# USB_FE1_1.net
KiCad netlist of a schematic drawn in Altium Designer
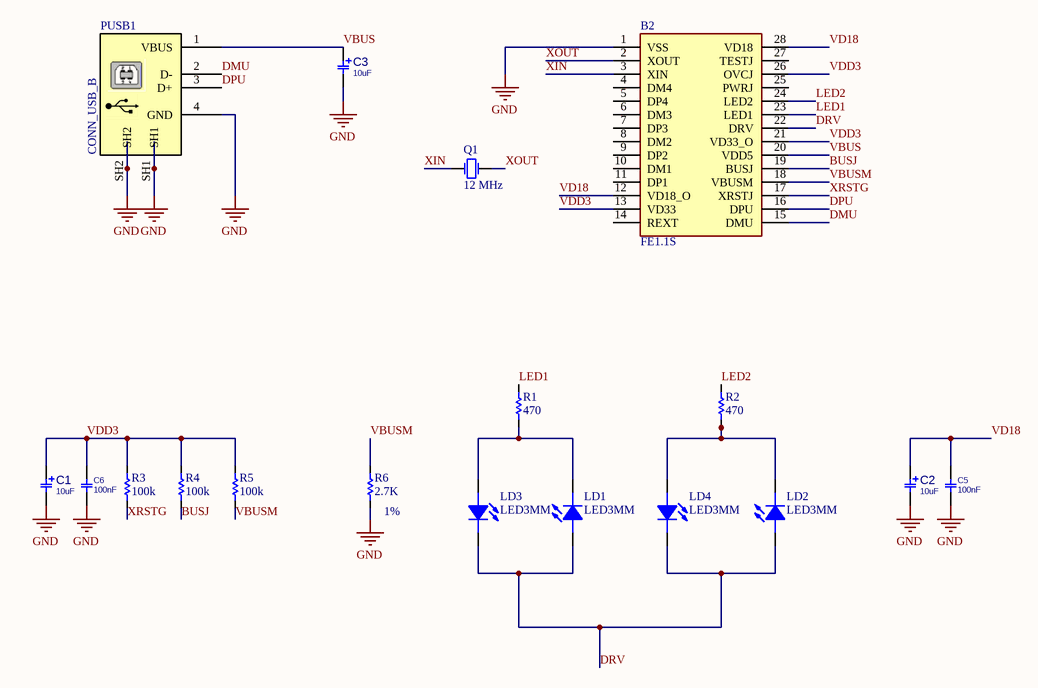
[diagram p0: USB_FE1.1.SchDoc]

(export (version "E")
  (design (tool "Eeschema 10.0.6"))
  (components
    (comp (ref "B2")
      (value "FE1.1S")
      (footprint "SOP64P600X175-28N")
      (description "USB 2.0 HIGH SPEED 4-PORT HUB CONTROLLER")
      (libsource (lib "FE1.1") (part "FE1.1S"))
    )
    (comp (ref "C1")
      (value "10uF")
      (footprint "C_EL_4X7")
      (description "CAP, THD, ELEC,")
      (fields (field (name "MANF_P#") "MANF_PART#") (field (name "MANF") "MANF"))
      (libsource (lib "PASSIVE") (part "CAP_THD_EL"))
    )
    (comp (ref "C2")
      (value "10uF")
      (footprint "C_EL_4X7")
      (description "CAP, THD, ELEC,")
      (fields (field (name "MANF_P#") "MANF_PART#") (field (name "MANF") "MANF"))
      (libsource (lib "PASSIVE") (part "CAP_THD_EL"))
    )
    (comp (ref "C3")
      (value "10uF")
      (footprint "C_EL_4X7")
      (description "CAP, THD, ELEC,")
      (fields (field (name "MANF_P#") "MANF_PART#") (field (name "MANF") "MANF"))
      (libsource (lib "PASSIVE") (part "CAP_THD_EL"))
    )
    (comp (ref "C5")
      (value "100nF")
      (footprint "C_CER_D3")
      (description "CAP, THD, CER MULTI LAYER,")
      (fields (field (name "MANF_P#") "MANF_PART#") (field (name "MANF") "MANF"))
      (libsource (lib "PASSIVE") (part "CAP_THD_CERML"))
    )
    (comp (ref "C6")
      (value "100nF")
      (footprint "C_CER_D3")
      (description "CAP, THD, CER MULTI LAYER,")
      (fields (field (name "MANF_P#") "MANF_PART#") (field (name "MANF") "MANF"))
      (libsource (lib "PASSIVE") (part "CAP_THD_CERML"))
    )
    (comp (ref "LD1")
      (value "LED3MM")
      (footprint "LED3mm_GRN")
      (description "Light Emitting Diode")
      (fields (field (name "DESIGNER") "Ali Hafizi"))
      (libsource (lib "4_5773615018641719593") (part "LED 3MM"))
    )
    (comp (ref "LD2")
      (value "LED3MM")
      (footprint "LED3mm_GRN")
      (description "Light Emitting Diode")
      (fields (field (name "DESIGNER") "Ali Hafizi"))
      (libsource (lib "4_5773615018641719593") (part "LED 3MM"))
    )
    (comp (ref "LD3")
      (value "LED3MM")
      (footprint "LED3mm_GRN")
      (description "Light Emitting Diode")
      (fields (field (name "DESIGNER") "Ali Hafizi"))
      (libsource (lib "4_5773615018641719593") (part "LED 3MM"))
    )
    (comp (ref "LD4")
      (value "LED3MM")
      (footprint "LED3mm_GRN")
      (description "Light Emitting Diode")
      (fields (field (name "DESIGNER") "Ali Hafizi"))
      (libsource (lib "4_5773615018641719593") (part "LED 3MM"))
    )
    (comp (ref "PUSB1")
      (value "CONN_USB_B")
      (footprint "USB_B_RA_THD")
      (description "CONN, USB, B, R/A, THD")
      (fields (field (name "MANF_P#") "292304-1") (field (name "MANF") "TE Connectivity"))
      (libsource (lib "Chila_PCB") (part "CONN_USB_B_RA_THD"))
    )
    (comp (ref "Q1")
      (value "12 MHz")
      (footprint "XTAL 16MHZ")
      (description "XTAL Crystal")
      (fields (field (name "DESIGNER") "ABBAS BASEREH"))
      (libsource (lib "4_5773615018641719593") (part "XTAL"))
    )
    (comp (ref "R1")
      (value "470")
      (footprint "Res-(1/4)")
      (description "Resistor")
      (fields (field (name "TOLERANCE") "5%") (field (name "POWER") "1/4 W"))
      (libsource (lib "altium mahdi") (part "Resistor"))
    )
    (comp (ref "R2")
      (value "470")
      (footprint "Res-(1/4)")
      (description "Resistor")
      (fields (field (name "TOLERANCE") "5%") (field (name "POWER") "1/4 W"))
      (libsource (lib "altium mahdi") (part "Resistor"))
    )
    (comp (ref "R3")
      (value "100k")
      (footprint "Res-(1/4)")
      (description "Resistor")
      (fields (field (name "TOLERANCE") "5%") (field (name "POWER") "1/4 W"))
      (libsource (lib "altium mahdi") (part "Resistor"))
    )
    (comp (ref "R4")
      (value "100k")
      (footprint "Res-(1/4)")
      (description "Resistor")
      (fields (field (name "TOLERANCE") "5%") (field (name "POWER") "1/4 W"))
      (libsource (lib "altium mahdi") (part "Resistor"))
    )
    (comp (ref "R5")
      (value "100k")
      (footprint "Res-(1/4)")
      (description "Resistor")
      (fields (field (name "TOLERANCE") "5%") (field (name "POWER") "1/4 W"))
      (libsource (lib "altium mahdi") (part "Resistor"))
    )
    (comp (ref "R6")
      (value "2.7K")
      (footprint "Res-(1/4)")
      (description "Resistor")
      (fields (field (name "TOLERANCE") "1%") (field (name "POWER") "1/4 W"))
      (libsource (lib "altium mahdi") (part "Resistor"))
    )
  )
  (nets
    (net (code "1") (name "/BUSJ") (class "Default")
      (node (ref "B2") (pin "19") (pinfunction "BUSJ_19") (pintype "passive"))
      (node (ref "R4") (pin "1") (pinfunction "1_1") (pintype "passive"))
    )
    (net (code "2") (name "/DMU") (class "Default")
      (node (ref "B2") (pin "15") (pinfunction "DMU_15") (pintype "passive"))
      (node (ref "PUSB1") (pin "2") (pinfunction "D-_2") (pintype "passive"))
    )
    (net (code "3") (name "/DPU") (class "Default")
      (node (ref "B2") (pin "16") (pinfunction "DPU_16") (pintype "passive"))
      (node (ref "PUSB1") (pin "3") (pinfunction "D+_3") (pintype "passive"))
    )
    (net (code "4") (name "/DRV") (class "Default")
      (node (ref "B2") (pin "22") (pinfunction "DRV_22") (pintype "passive"))
      (node (ref "LD1") (pin "1") (pinfunction "ANODE_1") (pintype "passive"))
      (node (ref "LD2") (pin "1") (pinfunction "ANODE_1") (pintype "passive"))
      (node (ref "LD3") (pin "2") (pinfunction "CATHODE_2") (pintype "passive"))
      (node (ref "LD4") (pin "2") (pinfunction "CATHODE_2") (pintype "passive"))
    )
    (net (code "5") (name "/LED1") (class "Default")
      (node (ref "B2") (pin "23") (pinfunction "LED1_23") (pintype "passive"))
      (node (ref "R1") (pin "2") (pinfunction "2_2") (pintype "passive"))
    )
    (net (code "6") (name "/LED2") (class "Default")
      (node (ref "B2") (pin "24") (pinfunction "LED2_24") (pintype "passive"))
      (node (ref "R2") (pin "2") (pinfunction "2_2") (pintype "passive"))
    )
    (net (code "7") (name "/VBUS") (class "Default")
      (node (ref "B2") (pin "20") (pinfunction "VDD5_20") (pintype "passive"))
      (node (ref "C3") (pin "1") (pinfunction "1_1") (pintype "passive"))
      (node (ref "PUSB1") (pin "1") (pinfunction "VBUS_1") (pintype "power_in"))
    )
    (net (code "8") (name "/VBUSM") (class "Default")
      (node (ref "B2") (pin "18") (pinfunction "VBUSM_18") (pintype "passive"))
      (node (ref "R5") (pin "1") (pinfunction "1_1") (pintype "passive"))
      (node (ref "R6") (pin "2") (pinfunction "2_2") (pintype "passive"))
    )
    (net (code "9") (name "/VD18") (class "Default")
      (node (ref "B2") (pin "12") (pinfunction "VD18_O_12") (pintype "passive"))
      (node (ref "B2") (pin "28") (pinfunction "VD18_28") (pintype "passive"))
      (node (ref "C2") (pin "1") (pinfunction "1_1") (pintype "passive"))
      (node (ref "C5") (pin "2") (pinfunction "2_2") (pintype "passive"))
    )
    (net (code "10") (name "/VDD3") (class "Default")
      (node (ref "B2") (pin "13") (pinfunction "VD33_13") (pintype "passive"))
      (node (ref "B2") (pin "21") (pinfunction "VD33_O_21") (pintype "passive"))
      (node (ref "B2") (pin "26") (pinfunction "OVCJ_26") (pintype "passive"))
      (node (ref "C1") (pin "1") (pinfunction "1_1") (pintype "passive"))
      (node (ref "C6") (pin "2") (pinfunction "2_2") (pintype "passive"))
      (node (ref "R3") (pin "2") (pinfunction "2_2") (pintype "passive"))
      (node (ref "R4") (pin "2") (pinfunction "2_2") (pintype "passive"))
      (node (ref "R5") (pin "2") (pinfunction "2_2") (pintype "passive"))
    )
    (net (code "11") (name "/XIN") (class "Default")
      (node (ref "B2") (pin "3") (pinfunction "XIN_3") (pintype "passive"))
      (node (ref "Q1") (pin "1") (pinfunction "OSC1_1") (pintype "passive"))
    )
    (net (code "12") (name "/XOUT") (class "Default")
      (node (ref "B2") (pin "2") (pinfunction "XOUT_2") (pintype "passive"))
      (node (ref "Q1") (pin "2") (pinfunction "OSC2_2") (pintype "passive"))
    )
    (net (code "13") (name "/XRSTG") (class "Default")
      (node (ref "B2") (pin "17") (pinfunction "XRSTJ_17") (pintype "passive"))
      (node (ref "R3") (pin "1") (pinfunction "1_1") (pintype "passive"))
    )
    (net (code "14") (name "GND") (class "Default")
      (node (ref "B2") (pin "1") (pinfunction "VSS_1") (pintype "passive"))
      (node (ref "C1") (pin "2") (pinfunction "2_2") (pintype "passive"))
      (node (ref "C2") (pin "2") (pinfunction "2_2") (pintype "passive"))
      (node (ref "C3") (pin "2") (pinfunction "2_2") (pintype "passive"))
      (node (ref "C5") (pin "1") (pinfunction "1_1") (pintype "passive"))
      (node (ref "C6") (pin "1") (pinfunction "1_1") (pintype "passive"))
      (node (ref "PUSB1") (pin "4") (pinfunction "GND_4") (pintype "power_in"))
      (node (ref "PUSB1") (pin "SH1") (pinfunction "SH1_SH1") (pintype "passive"))
      (node (ref "PUSB1") (pin "SH2") (pinfunction "SH2_SH2") (pintype "passive"))
      (node (ref "R6") (pin "1") (pinfunction "1_1") (pintype "passive"))
    )
    (net (code "15") (name "Net-(LD1-CATHODE)") (class "Default")
      (node (ref "LD1") (pin "2") (pinfunction "CATHODE_2") (pintype "passive"))
      (node (ref "LD3") (pin "1") (pinfunction "ANODE_1") (pintype "passive"))
      (node (ref "R1") (pin "1") (pinfunction "1_1") (pintype "passive"))
    )
    (net (code "16") (name "Net-(LD2-CATHODE)") (class "Default")
      (node (ref "LD2") (pin "2") (pinfunction "CATHODE_2") (pintype "passive"))
      (node (ref "LD4") (pin "1") (pinfunction "ANODE_1") (pintype "passive"))
      (node (ref "R2") (pin "1") (pinfunction "1_1") (pintype "passive"))
    )
    (net (code "17") (name "unconnected-(B2-DM1-Pad10)") (class "Default")
      (node (ref "B2") (pin "10") (pinfunction "DM1_10") (pintype "passive"))
    )
    (net (code "18") (name "unconnected-(B2-DM2-Pad8)") (class "Default")
      (node (ref "B2") (pin "8") (pinfunction "DM2_8") (pintype "passive"))
    )
    (net (code "19") (name "unconnected-(B2-DM3-Pad6)") (class "Default")
      (node (ref "B2") (pin "6") (pinfunction "DM3_6") (pintype "passive"))
    )
    (net (code "20") (name "unconnected-(B2-DM4-Pad4)") (class "Default")
      (node (ref "B2") (pin "4") (pinfunction "DM4_4") (pintype "passive"))
    )
    (net (code "21") (name "unconnected-(B2-DP1-Pad11)") (class "Default")
      (node (ref "B2") (pin "11") (pinfunction "DP1_11") (pintype "passive"))
    )
    (net (code "22") (name "unconnected-(B2-DP2-Pad9)") (class "Default")
      (node (ref "B2") (pin "9") (pinfunction "DP2_9") (pintype "passive"))
    )
    (net (code "23") (name "unconnected-(B2-DP3-Pad7)") (class "Default")
      (node (ref "B2") (pin "7") (pinfunction "DP3_7") (pintype "passive"))
    )
    (net (code "24") (name "unconnected-(B2-DP4-Pad5)") (class "Default")
      (node (ref "B2") (pin "5") (pinfunction "DP4_5") (pintype "passive"))
    )
    (net (code "25") (name "unconnected-(B2-PWRJ-Pad25)") (class "Default")
      (node (ref "B2") (pin "25") (pinfunction "PWRJ_25") (pintype "passive"))
    )
    (net (code "26") (name "unconnected-(B2-REXT-Pad14)") (class "Default")
      (node (ref "B2") (pin "14") (pinfunction "REXT_14") (pintype "passive"))
    )
    (net (code "27") (name "unconnected-(B2-TESTJ-Pad27)") (class "Default")
      (node (ref "B2") (pin "27") (pinfunction "TESTJ_27") (pintype "passive"))
    )
  )
)
